# DIMMER.net
KiCad netlist of a schematic drawn in Altium Designer
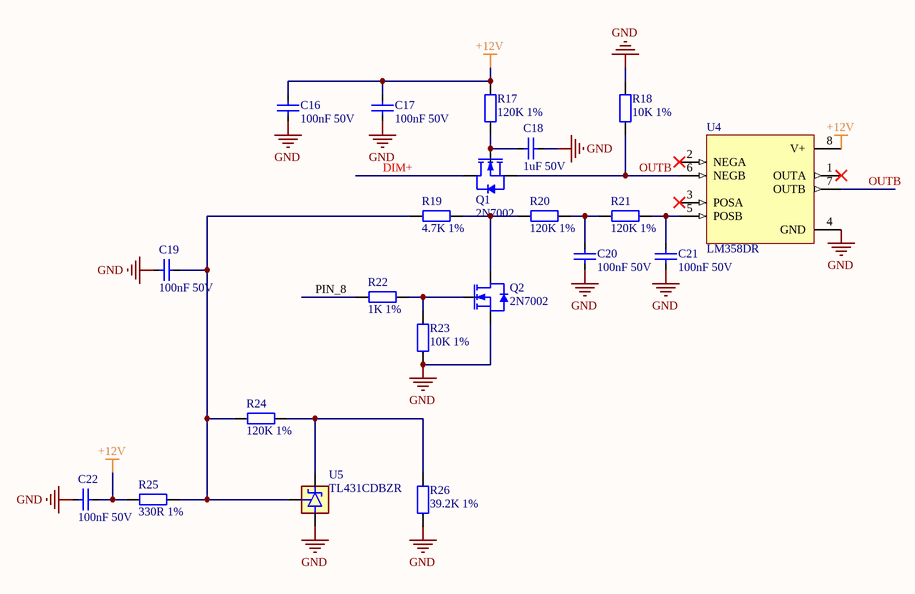
[diagram p0: DIMMER.SchDoc]

(export (version "E")
  (design (tool "Eeschema 10.0.6"))
  (components
    (comp (ref "C16")
      (value "100nF 50V")
      (footprint "CAP_SMD_0805")
      (description "0.1 µF ±10% 50V Ceramic Capacitor X7R 0805 (2012 Metric)")
      (fields
        (field (name "MANUFACTURER") "YAGEO")
        (field (name "MANUFACTURE PART NUMBER") "CC0805KRX7R9BB104")
      )
      (libsource (lib "Nhatkhongbuon") (part "C0805_MLCC_100nF_50V"))
    )
    (comp (ref "C17")
      (value "100nF 50V")
      (footprint "CAP_SMD_0805")
      (description "0.1 µF ±10% 50V Ceramic Capacitor X7R 0805 (2012 Metric)")
      (fields
        (field (name "MANUFACTURER") "YAGEO")
        (field (name "MANUFACTURE PART NUMBER") "CC0805KRX7R9BB104")
      )
      (libsource (lib "Nhatkhongbuon") (part "C0805_MLCC_100nF_50V"))
    )
    (comp (ref "C18")
      (value "1uF 50V")
      (footprint "CAP_SMD_0805")
      (description "1 µF ±10% 50V Ceramic Capacitor X7R 0805 (2012 Metric)")
      (fields
        (field (name "MANUFACTURER") "Samsung Electro-Mechanics")
        (field (name "MANUFACTURE PART NUMBER") "CL21B105KBFNNNG")
      )
      (libsource (lib "Nhatkhongbuon") (part "C0805_MLCC_1uF_50V"))
    )
    (comp (ref "C19")
      (value "100nF 50V")
      (footprint "CAP_SMD_0805")
      (description "0.1 µF ±10% 50V Ceramic Capacitor X7R 0805 (2012 Metric)")
      (fields
        (field (name "MANUFACTURER") "YAGEO")
        (field (name "MANUFACTURE PART NUMBER") "CC0805KRX7R9BB104")
      )
      (libsource (lib "Nhatkhongbuon") (part "C0805_MLCC_100nF_50V"))
    )
    (comp (ref "C20")
      (value "100nF 50V")
      (footprint "CAP_SMD_0805")
      (description "0.1 µF ±10% 50V Ceramic Capacitor X7R 0805 (2012 Metric)")
      (fields
        (field (name "MANUFACTURER") "YAGEO")
        (field (name "MANUFACTURE PART NUMBER") "CC0805KRX7R9BB104")
      )
      (libsource (lib "Nhatkhongbuon") (part "C0805_MLCC_100nF_50V"))
    )
    (comp (ref "C21")
      (value "100nF 50V")
      (footprint "CAP_SMD_0805")
      (description "0.1 µF ±10% 50V Ceramic Capacitor X7R 0805 (2012 Metric)")
      (fields
        (field (name "MANUFACTURER") "YAGEO")
        (field (name "MANUFACTURE PART NUMBER") "CC0805KRX7R9BB104")
      )
      (libsource (lib "Nhatkhongbuon") (part "C0805_MLCC_100nF_50V"))
    )
    (comp (ref "C22")
      (value "100nF 50V")
      (footprint "CAP_SMD_0805")
      (description "0.1 µF ±10% 50V Ceramic Capacitor X7R 0805 (2012 Metric)")
      (fields
        (field (name "MANUFACTURER") "YAGEO")
        (field (name "MANUFACTURE PART NUMBER") "CC0805KRX7R9BB104")
      )
      (libsource (lib "Nhatkhongbuon") (part "C0805_MLCC_100nF_50V"))
    )
    (comp (ref "Q1")
      (value "2N7002")
      (footprint "SOT-23-3")
      (description "N-Channel 60 V 115mA (Ta) 200mW (Ta) Surface Mount SOT-23-3")
      (fields (field (name "MANUFACTURER") "onsemi"))
      (libsource (lib "Nhatkhongbuon") (part "2N7002"))
    )
    (comp (ref "Q2")
      (value "2N7002")
      (footprint "SOT-23-3")
      (description "N-Channel 60 V 115mA (Ta) 200mW (Ta) Surface Mount SOT-23-3")
      (fields (field (name "MANUFACTURER") "onsemi"))
      (libsource (lib "Nhatkhongbuon") (part "2N7002"))
    )
    (comp (ref "R17")
      (value "120K 1%")
      (footprint "RES_SMD_0805")
      (description "120 kOhms ±1% 0.125W, 1/8W Chip Resistor 0805 (2012 Metric) Moisture Resistant Thick Film")
      (fields
        (field (name "MANUFACTURER") "YAGEO")
        (field (name "MANUFACTURE PART NUMBER") "RC0805FR-07120KL")
      )
      (libsource (lib "Nhatkhongbuon") (part "R0805_120K"))
    )
    (comp (ref "R18")
      (value "10K 1%")
      (footprint "RES_SMD_0805")
      (description "10 kOhms ±1% 0.125W, 1/8W Chip Resistor 0805 (2012 Metric) Moisture Resistant Thick Film")
      (fields
        (field (name "MANUFACTURER") "YAGEO")
        (field (name "MANUFACTURE PART NUMBER") "RC0805FR-0710KL")
      )
      (libsource (lib "Nhatkhongbuon") (part "R0805_10K"))
    )
    (comp (ref "R19")
      (value "4.7K 1%")
      (footprint "RES_SMD_0805")
      (description "4.7 kOhms ±1% 0.125W, 1/8W Chip Resistor 0805 (2012 Metric) Thick Film")
      (fields
        (field (name "MANUFACTURER") "Vishay Dale")
        (field (name "MANUFACTURE PART NUMBER") "CRCW08054K70FKEAC")
      )
      (libsource (lib "Nhatkhongbuon") (part "R0805_4.7K"))
    )
    (comp (ref "R20")
      (value "120K 1%")
      (footprint "RES_SMD_0805")
      (description "120 kOhms ±1% 0.125W, 1/8W Chip Resistor 0805 (2012 Metric) Moisture Resistant Thick Film")
      (fields
        (field (name "MANUFACTURER") "YAGEO")
        (field (name "MANUFACTURE PART NUMBER") "RC0805FR-07120KL")
      )
      (libsource (lib "Nhatkhongbuon") (part "R0805_120K"))
    )
    (comp (ref "R21")
      (value "120K 1%")
      (footprint "RES_SMD_0805")
      (description "120 kOhms ±1% 0.125W, 1/8W Chip Resistor 0805 (2012 Metric) Moisture Resistant Thick Film")
      (fields
        (field (name "MANUFACTURER") "YAGEO")
        (field (name "MANUFACTURE PART NUMBER") "RC0805FR-07120KL")
      )
      (libsource (lib "Nhatkhongbuon") (part "R0805_120K"))
    )
    (comp (ref "R22")
      (value "1K 1%")
      (footprint "RES_SMD_0805")
      (description "1 kOhms ±1% 0.125W, 1/8W Chip Resistor 0805 (2012 Metric) Moisture Resistant Thick Film")
      (fields
        (field (name "MANUFACTURER") "YAGEO")
        (field (name "MANUFACTURE PART NUMBER") "311-1.00KCRCT-ND")
      )
      (libsource (lib "Nhatkhongbuon") (part "R0805_1K"))
    )
    (comp (ref "R23")
      (value "10K 1%")
      (footprint "RES_SMD_0805")
      (description "10 kOhms ±1% 0.125W, 1/8W Chip Resistor 0805 (2012 Metric) Moisture Resistant Thick Film")
      (fields
        (field (name "MANUFACTURER") "YAGEO")
        (field (name "MANUFACTURE PART NUMBER") "RC0805FR-0710KL")
      )
      (libsource (lib "Nhatkhongbuon") (part "R0805_10K"))
    )
    (comp (ref "R24")
      (value "120K 1%")
      (footprint "RES_SMD_0805")
      (description "120 kOhms ±1% 0.125W, 1/8W Chip Resistor 0805 (2012 Metric) Moisture Resistant Thick Film")
      (fields
        (field (name "MANUFACTURER") "YAGEO")
        (field (name "MANUFACTURE PART NUMBER") "RC0805FR-07120KL")
      )
      (libsource (lib "Nhatkhongbuon") (part "R0805_120K"))
    )
    (comp (ref "R25")
      (value "330R 1%")
      (footprint "RES_SMD_0805")
      (description "330 Ohms ±1% 0.125W, 1/8W Chip Resistor 0805 (2012 Metric) Automotive AEC-Q200 Thick Film")
      (fields
        (field (name "MANUFACTURER") "Stackpole Electronics Inc")
        (field (name "MANUFACTURE PART NUMBER") "RMCF0805FT330R")
      )
      (libsource (lib "Nhatkhongbuon") (part "R0805_330R"))
    )
    (comp (ref "R26")
      (value "39.2K 1%")
      (footprint "RES_SMD_0805")
      (description "39.2 kOhms ±1% 0.125W, 1/8W Chip Resistor 0805 (2012 Metric) Moisture Resistant Thick Film")
      (fields
        (field (name "MANUFACTURER") "YAGEO")
        (field (name "MANUFACTURE PART NUMBER") "RC0805FR-0739K2L")
      )
      (libsource (lib "Nhatkhongbuon") (part "R0805_39.2K"))
    )
    (comp (ref "U4")
      (value "LM358DR")
      (footprint "8 - SOIC")
      (description "General Purpose Amplifier 2 Circuit 8-SOIC")
      (fields (field (name "MANUFACTURER") "Texas Instruments"))
      (libsource (lib "Nhatkhongbuon") (part "LM358DR"))
    )
    (comp (ref "U5")
      (value "TL431CDBZR")
      (footprint "SOT-23-3")
      (description "Shunt Voltage Reference IC Adjustable 2.495V 36 VV ±2.2% 100 mA SOT-23-3")
      (fields (field (name "MANUFACTURER") "Texas Instruments"))
      (libsource (lib "Nhatkhongbuon") (part "TL431CDBZR"))
    )
  )
  (nets
    (net (code "1") (name "+12V") (class "Default")
      (node (ref "C16") (pin "2") (pinfunction "2_2") (pintype "passive"))
      (node (ref "C17") (pin "2") (pinfunction "2_2") (pintype "passive"))
      (node (ref "C22") (pin "2") (pinfunction "2_2") (pintype "passive"))
      (node (ref "R17") (pin "2") (pinfunction "2_2") (pintype "passive"))
      (node (ref "R25") (pin "1") (pinfunction "1_1") (pintype "passive"))
      (node (ref "U4") (pin "8") (pinfunction "V+_8") (pintype "passive"))
    )
    (net (code "2") (name "/DIM+") (class "Default")
      (node (ref "Q1") (pin "2") (pinfunction "D_2") (pintype "passive"))
    )
    (net (code "3") (name "/OUTB") (class "Default")
      (node (ref "Q1") (pin "3") (pinfunction "S_3") (pintype "passive"))
      (node (ref "R18") (pin "1") (pinfunction "1_1") (pintype "passive"))
      (node (ref "U4") (pin "6") (pinfunction "NEGB_6") (pintype "input"))
      (node (ref "U4") (pin "7") (pinfunction "OUTB_7") (pintype "output"))
    )
    (net (code "4") (name "/PIN_8") (class "Default")
      (node (ref "R22") (pin "1") (pinfunction "1_1") (pintype "passive"))
    )
    (net (code "5") (name "GND") (class "Default")
      (node (ref "C16") (pin "1") (pinfunction "1_1") (pintype "passive"))
      (node (ref "C17") (pin "1") (pinfunction "1_1") (pintype "passive"))
      (node (ref "C18") (pin "2") (pinfunction "2_2") (pintype "passive"))
      (node (ref "C19") (pin "1") (pinfunction "1_1") (pintype "passive"))
      (node (ref "C20") (pin "1") (pinfunction "1_1") (pintype "passive"))
      (node (ref "C21") (pin "1") (pinfunction "1_1") (pintype "passive"))
      (node (ref "C22") (pin "1") (pinfunction "1_1") (pintype "passive"))
      (node (ref "Q2") (pin "3") (pinfunction "S_3") (pintype "passive"))
      (node (ref "R18") (pin "2") (pinfunction "2_2") (pintype "passive"))
      (node (ref "R23") (pin "1") (pinfunction "1_1") (pintype "passive"))
      (node (ref "R26") (pin "1") (pinfunction "1_1") (pintype "passive"))
      (node (ref "U4") (pin "4") (pinfunction "GND_4") (pintype "passive"))
      (node (ref "U5") (pin "3") (pinfunction "ANODE_3") (pintype "passive"))
    )
    (net (code "6") (name "Net-(C20-Pad2)") (class "Default")
      (node (ref "C20") (pin "2") (pinfunction "2_2") (pintype "passive"))
      (node (ref "R20") (pin "2") (pinfunction "2_2") (pintype "passive"))
      (node (ref "R21") (pin "1") (pinfunction "1_1") (pintype "passive"))
    )
    (net (code "7") (name "Net-(Q1-G)") (class "Default")
      (node (ref "C18") (pin "1") (pinfunction "1_1") (pintype "passive"))
      (node (ref "Q1") (pin "1") (pinfunction "G_1") (pintype "passive"))
      (node (ref "R17") (pin "1") (pinfunction "1_1") (pintype "passive"))
    )
    (net (code "8") (name "Net-(Q2-D)") (class "Default")
      (node (ref "Q2") (pin "2") (pinfunction "D_2") (pintype "passive"))
      (node (ref "R19") (pin "2") (pinfunction "2_2") (pintype "passive"))
      (node (ref "R20") (pin "1") (pinfunction "1_1") (pintype "passive"))
    )
    (net (code "9") (name "Net-(Q2-G)") (class "Default")
      (node (ref "Q2") (pin "1") (pinfunction "G_1") (pintype "passive"))
      (node (ref "R22") (pin "2") (pinfunction "2_2") (pintype "passive"))
      (node (ref "R23") (pin "2") (pinfunction "2_2") (pintype "passive"))
    )
    (net (code "10") (name "Net-(U4-POSB)") (class "Default")
      (node (ref "C21") (pin "2") (pinfunction "2_2") (pintype "passive"))
      (node (ref "R21") (pin "2") (pinfunction "2_2") (pintype "passive"))
      (node (ref "U4") (pin "5") (pinfunction "POSB_5") (pintype "input"))
    )
    (net (code "11") (name "Net-(U5-CATHODE)") (class "Default")
      (node (ref "R24") (pin "2") (pinfunction "2_2") (pintype "passive"))
      (node (ref "R26") (pin "2") (pinfunction "2_2") (pintype "passive"))
      (node (ref "U5") (pin "1") (pinfunction "CATHODE_1") (pintype "passive"))
    )
    (net (code "12") (name "Net-(U5-REF)") (class "Default")
      (node (ref "C19") (pin "2") (pinfunction "2_2") (pintype "passive"))
      (node (ref "R19") (pin "1") (pinfunction "1_1") (pintype "passive"))
      (node (ref "R24") (pin "1") (pinfunction "1_1") (pintype "passive"))
      (node (ref "R25") (pin "2") (pinfunction "2_2") (pintype "passive"))
      (node (ref "U5") (pin "2") (pinfunction "REF_2") (pintype "passive"))
    )
    (net (code "13") (name "unconnected-(U4-NEGA-Pad2)") (class "Default")
      (node (ref "U4") (pin "2") (pinfunction "NEGA_2") (pintype "input+no_connect"))
    )
    (net (code "14") (name "unconnected-(U4-OUTA-Pad1)") (class "Default")
      (node (ref "U4") (pin "1") (pinfunction "OUTA_1") (pintype "output+no_connect"))
    )
    (net (code "15") (name "unconnected-(U4-POSA-Pad3)") (class "Default")
      (node (ref "U4") (pin "3") (pinfunction "POSA_3") (pintype "input+no_connect"))
    )
  )
)
